# SRK1201L_MODUL_CON.net
KiCad netlist of a schematic drawn in Altium Designer
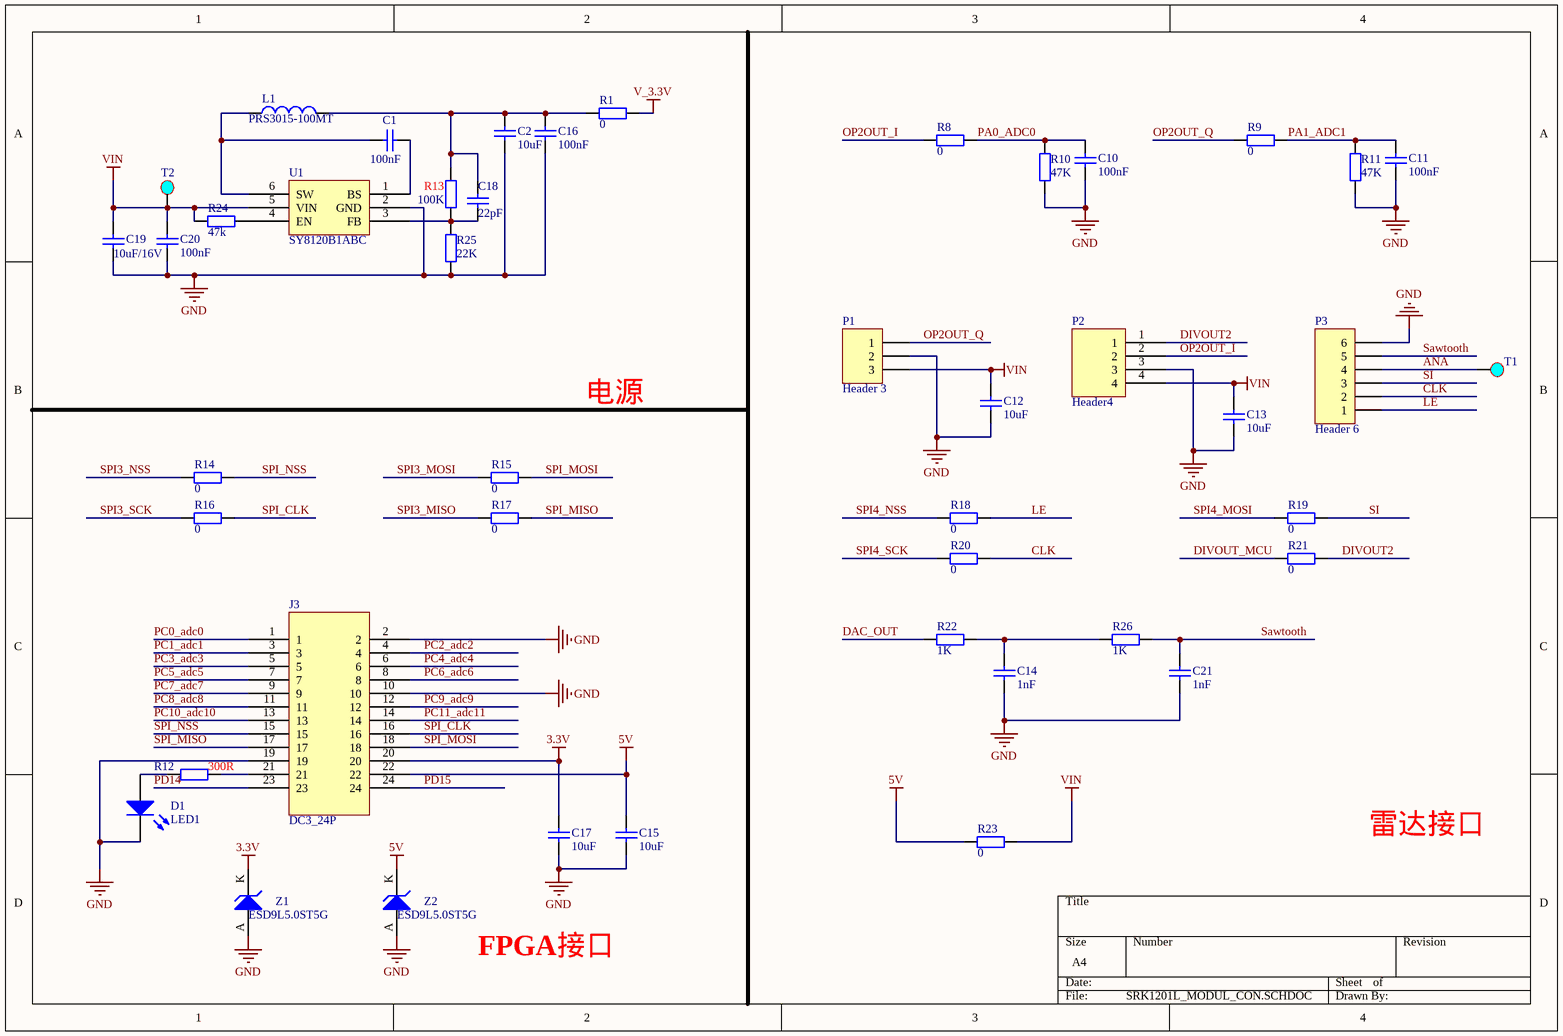
[diagram p0: SRK1201L_MODUL_CON.SCHDOC]

(export (version "E")
  (design (tool "Eeschema 10.0.6"))
  (components
    (comp (ref "C1")
      (value "100nF")
      (footprint "C0402")
      (description "Capacitor")
      (fields (field (name "PUBLISHER") "Altium Limited"))
      (libsource (lib "Miscellaneous Devices") (part "Cap"))
    )
    (comp (ref "C2")
      (value "10uF")
      (footprint "C0603")
      (description "Capacitor")
      (fields (field (name "PUBLISHER") "Altium Limited"))
      (libsource (lib "Miscellaneous Devices") (part "Cap"))
    )
    (comp (ref "C10")
      (value "100nF")
      (footprint "C0402")
      (description "Capacitor")
      (fields (field (name "PUBLISHER") "Altium Limited"))
      (libsource (lib "Miscellaneous Devices") (part "Cap"))
    )
    (comp (ref "C11")
      (value "100nF")
      (footprint "C0402")
      (description "Capacitor")
      (fields (field (name "PUBLISHER") "Altium Limited"))
      (libsource (lib "Miscellaneous Devices") (part "Cap"))
    )
    (comp (ref "C12")
      (value "10uF")
      (footprint "C0603")
      (description "Capacitor")
      (fields (field (name "PUBLISHER") "Altium Limited"))
      (libsource (lib "Miscellaneous Devices") (part "Cap"))
    )
    (comp (ref "C13")
      (value "10uF")
      (footprint "C0603")
      (description "Capacitor")
      (fields (field (name "PUBLISHER") "Altium Limited"))
      (libsource (lib "Miscellaneous Devices") (part "Cap"))
    )
    (comp (ref "C14")
      (value "1nF")
      (footprint "C0402")
      (description "Capacitor")
      (fields (field (name "PUBLISHER") "Altium Limited"))
      (libsource (lib "Miscellaneous Devices") (part "Cap"))
    )
    (comp (ref "C15")
      (value "10uF")
      (footprint "C0603")
      (description "Capacitor")
      (fields (field (name "PUBLISHER") "Altium Limited"))
      (libsource (lib "Miscellaneous Devices") (part "Cap"))
    )
    (comp (ref "C16")
      (value "100nF")
      (footprint "C0402")
      (description "Capacitor")
      (fields (field (name "PUBLISHER") "Altium Limited"))
      (libsource (lib "Miscellaneous Devices") (part "Cap"))
    )
    (comp (ref "C17")
      (value "10uF")
      (footprint "C0603")
      (description "Capacitor")
      (fields (field (name "PUBLISHER") "Altium Limited"))
      (libsource (lib "Miscellaneous Devices") (part "Cap"))
    )
    (comp (ref "C18")
      (value "22pF")
      (footprint "C0402")
      (description "Capacitor")
      (fields (field (name "PUBLISHER") "Altium Limited"))
      (libsource (lib "Miscellaneous Devices") (part "Cap"))
    )
    (comp (ref "C19")
      (value "10uF/16V")
      (footprint "C0603")
      (description "Capacitor")
      (fields (field (name "PUBLISHER") "Altium Limited"))
      (libsource (lib "Miscellaneous Devices") (part "Cap"))
    )
    (comp (ref "C20")
      (value "100nF")
      (footprint "C0402")
      (description "Capacitor")
      (fields (field (name "PUBLISHER") "Altium Limited"))
      (libsource (lib "Miscellaneous Devices") (part "Cap"))
    )
    (comp (ref "C21")
      (value "1nF")
      (footprint "C0402")
      (description "Capacitor")
      (fields (field (name "PUBLISHER") "Altium Limited"))
      (libsource (lib "Miscellaneous Devices") (part "Cap"))
    )
    (comp (ref "D1")
      (value "LED1")
      (footprint "LED-0603")
      (description "Typical RED GaAs LED")
      (fields (field (name "PUBLISHER") "Altium Limited"))
      (libsource (lib "Miscellaneous Devices") (part "LED1"))
    )
    (comp (ref "J3")
      (value "DC3_24P")
      (footprint "CON2.0-12X2 -SWAP")
      (libsource (lib "Schlib1") (part "DC3_24P"))
    )
    (comp (ref "L1")
      (value "PRS3015-100MT")
      (footprint "PRS3015")
      (description "Inductor")
      (fields (field (name "PUBLISHER") "Altium Limited"))
      (libsource (lib "Miscellaneous Devices") (part "Inductor"))
    )
    (comp (ref "P1")
      (value "Header 3")
      (footprint "HDR1X3-2.54")
      (description "Header, 3-Pin")
      (fields (field (name "PUBLISHER") "Altium Limited"))
      (libsource (lib "Miscellaneous Connectors") (part "Header 3"))
    )
    (comp (ref "P2") (value "Header4") (footprint "J4") (libsource (lib "Schlib1") (part "J4")))
    (comp (ref "P3")
      (value "Header 6")
      (footprint "HDR1X6")
      (description "Header, 6-Pin")
      (fields (field (name "PUBLISHER") "Altium Limited"))
      (libsource (lib "Miscellaneous Connectors") (part "Header 6"))
    )
    (comp (ref "R1")
      (value "0")
      (footprint "R0402")
      (description "Resistor")
      (fields (field (name "PUBLISHER") "Altium Limited"))
      (libsource (lib "Miscellaneous Devices") (part "Res2"))
    )
    (comp (ref "R8")
      (value "0")
      (footprint "R0402")
      (description "Resistor")
      (fields (field (name "PUBLISHER") "Altium Limited"))
      (libsource (lib "Miscellaneous Devices") (part "Res2"))
    )
    (comp (ref "R9")
      (value "0")
      (footprint "R0402")
      (description "Resistor")
      (fields (field (name "PUBLISHER") "Altium Limited"))
      (libsource (lib "Miscellaneous Devices") (part "Res2"))
    )
    (comp (ref "R10")
      (value "47K")
      (footprint "R0402")
      (description "Resistor")
      (fields (field (name "PUBLISHER") "Altium Limited"))
      (libsource (lib "") (part "Res2_1"))
    )
    (comp (ref "R11")
      (value "47K")
      (footprint "R0402")
      (description "Resistor")
      (fields (field (name "PUBLISHER") "Altium Limited"))
      (libsource (lib "") (part "Res2_1"))
    )
    (comp (ref "R12")
      (value "300R")
      (footprint "R0402")
      (description "Resistor")
      (fields (field (name "PUBLISHER") "Altium Limited"))
      (libsource (lib "Miscellaneous Devices") (part "Res2"))
    )
    (comp (ref "R13")
      (value "100K")
      (footprint "R0402")
      (description "Resistor")
      (fields (field (name "PUBLISHER") "Altium Limited"))
      (libsource (lib "") (part "Res2_1"))
    )
    (comp (ref "R14")
      (value "0")
      (footprint "R0402")
      (description "Resistor")
      (fields (field (name "PUBLISHER") "Altium Limited"))
      (libsource (lib "Miscellaneous Devices") (part "Res2"))
    )
    (comp (ref "R15")
      (value "0")
      (footprint "R0402")
      (description "Resistor")
      (fields (field (name "PUBLISHER") "Altium Limited"))
      (libsource (lib "Miscellaneous Devices") (part "Res2"))
    )
    (comp (ref "R16")
      (value "0")
      (footprint "R0402")
      (description "Resistor")
      (fields (field (name "PUBLISHER") "Altium Limited"))
      (libsource (lib "Miscellaneous Devices") (part "Res2"))
    )
    (comp (ref "R17")
      (value "0")
      (footprint "R0402")
      (description "Resistor")
      (fields (field (name "PUBLISHER") "Altium Limited"))
      (libsource (lib "Miscellaneous Devices") (part "Res2"))
    )
    (comp (ref "R18")
      (value "0")
      (footprint "R0402")
      (description "Resistor")
      (fields (field (name "PUBLISHER") "Altium Limited"))
      (libsource (lib "Miscellaneous Devices") (part "Res2"))
    )
    (comp (ref "R19")
      (value "0")
      (footprint "R0402")
      (description "Resistor")
      (fields (field (name "PUBLISHER") "Altium Limited"))
      (libsource (lib "Miscellaneous Devices") (part "Res2"))
    )
    (comp (ref "R20")
      (value "0")
      (footprint "R0402")
      (description "Resistor")
      (fields (field (name "PUBLISHER") "Altium Limited"))
      (libsource (lib "Miscellaneous Devices") (part "Res2"))
    )
    (comp (ref "R21")
      (value "0")
      (footprint "R0402")
      (description "Resistor")
      (fields (field (name "PUBLISHER") "Altium Limited"))
      (libsource (lib "Miscellaneous Devices") (part "Res2"))
    )
    (comp (ref "R22")
      (value "1K")
      (footprint "R0402")
      (description "Resistor")
      (fields (field (name "PUBLISHER") "Altium Limited"))
      (libsource (lib "Miscellaneous Devices") (part "Res2"))
    )
    (comp (ref "R23")
      (value "0")
      (footprint "R0402")
      (description "Resistor")
      (fields (field (name "PUBLISHER") "Altium Limited"))
      (libsource (lib "Miscellaneous Devices") (part "Res2"))
    )
    (comp (ref "R24")
      (value "47k")
      (footprint "R0402")
      (description "Resistor")
      (fields (field (name "PUBLISHER") "Altium Limited"))
      (libsource (lib "Miscellaneous Devices") (part "Res2"))
    )
    (comp (ref "R25")
      (value "22K")
      (footprint "R0402")
      (description "Resistor")
      (fields (field (name "PUBLISHER") "Altium Limited"))
      (libsource (lib "") (part "Res2_1"))
    )
    (comp (ref "R26")
      (value "1K")
      (footprint "R0402")
      (description "Resistor")
      (fields (field (name "PUBLISHER") "Altium Limited"))
      (libsource (lib "Miscellaneous Devices") (part "Res2"))
    )
    (comp (ref "T1")
      (value "~")
      (footprint "TestPoints")
      (description "TestPoints")
      (libsource (lib "标准原理图库（特种板）") (part "TestPoints"))
    )
    (comp (ref "T2")
      (value "~")
      (footprint "TestPoints-0.7")
      (description "TestPoints")
      (libsource (lib "标准原理图库（特种板）") (part "TestPoints"))
    )
    (comp (ref "U1") (value "SY8120B1ABC") (footprint "SOT-23-6") (libsource (lib "Schlib1") (part "H9108")))
    (comp (ref "Z1")
      (value "ESD9L5.0ST5G")
      (footprint "SOD-923")
      (description "Zener Diode")
      (fields (field (name "PUBLISHER") "Altium Limited"))
      (libsource (lib "Miscellaneous Devices") (part "D Zener"))
    )
    (comp (ref "Z2")
      (value "ESD9L5.0ST5G")
      (footprint "SOD-923")
      (description "Zener Diode")
      (fields (field (name "PUBLISHER") "Altium Limited"))
      (libsource (lib "Miscellaneous Devices") (part "D Zener"))
    )
  )
  (nets
    (net (code "1") (name "/ANA") (class "Default")
      (node (ref "P3") (pin "4") (pinfunction "4_4") (pintype "passive"))
      (node (ref "T1") (pin "1") (pinfunction "1_1") (pintype "passive"))
    )
    (net (code "2") (name "/CLK") (class "Default")
      (node (ref "P3") (pin "2") (pinfunction "2_2") (pintype "passive"))
      (node (ref "R20") (pin "1") (pinfunction "1_1") (pintype "passive"))
    )
    (net (code "3") (name "/DAC_OUT") (class "Default")
      (node (ref "R22") (pin "2") (pinfunction "2_2") (pintype "passive"))
    )
    (net (code "4") (name "/DIVOUT2") (class "Default")
      (node (ref "P2") (pin "1") (pinfunction "1_1") (pintype "passive"))
      (node (ref "R21") (pin "1") (pinfunction "1_1") (pintype "passive"))
    )
    (net (code "5") (name "/DIVOUT_MCU") (class "Default")
      (node (ref "R21") (pin "2") (pinfunction "2_2") (pintype "passive"))
    )
    (net (code "6") (name "/LE") (class "Default")
      (node (ref "P3") (pin "1") (pinfunction "1_1") (pintype "passive"))
      (node (ref "R18") (pin "1") (pinfunction "1_1") (pintype "passive"))
    )
    (net (code "7") (name "/OP2OUT_I") (class "Default")
      (node (ref "P2") (pin "2") (pinfunction "2_2") (pintype "passive"))
      (node (ref "R8") (pin "2") (pinfunction "2_2") (pintype "passive"))
    )
    (net (code "8") (name "/OP2OUT_Q") (class "Default")
      (node (ref "P1") (pin "1") (pinfunction "1_1") (pintype "passive"))
      (node (ref "R9") (pin "2") (pinfunction "2_2") (pintype "passive"))
    )
    (net (code "9") (name "/PA0_ADC0") (class "Default")
      (node (ref "C10") (pin "1") (pinfunction "1_1") (pintype "passive"))
      (node (ref "R10") (pin "2") (pinfunction "2_2") (pintype "passive"))
      (node (ref "R8") (pin "1") (pinfunction "1_1") (pintype "passive"))
    )
    (net (code "10") (name "/PA1_ADC1") (class "Default")
      (node (ref "C11") (pin "1") (pinfunction "1_1") (pintype "passive"))
      (node (ref "R11") (pin "2") (pinfunction "2_2") (pintype "passive"))
      (node (ref "R9") (pin "1") (pinfunction "1_1") (pintype "passive"))
    )
    (net (code "11") (name "/PC0_adc0") (class "Default")
      (node (ref "J3") (pin "1") (pinfunction "1_1") (pintype "passive"))
    )
    (net (code "12") (name "/PC1_adc1") (class "Default")
      (node (ref "J3") (pin "3") (pinfunction "3_3") (pintype "passive"))
    )
    (net (code "13") (name "/PC2_adc2") (class "Default")
      (node (ref "J3") (pin "4") (pinfunction "4_4") (pintype "passive"))
    )
    (net (code "14") (name "/PC3_adc3") (class "Default")
      (node (ref "J3") (pin "5") (pinfunction "5_5") (pintype "passive"))
    )
    (net (code "15") (name "/PC4_adc4") (class "Default")
      (node (ref "J3") (pin "6") (pinfunction "6_6") (pintype "passive"))
    )
    (net (code "16") (name "/PC5_adc5") (class "Default")
      (node (ref "J3") (pin "7") (pinfunction "7_7") (pintype "passive"))
    )
    (net (code "17") (name "/PC6_adc6") (class "Default")
      (node (ref "J3") (pin "8") (pinfunction "8_8") (pintype "passive"))
    )
    (net (code "18") (name "/PC7_adc7") (class "Default")
      (node (ref "J3") (pin "9") (pinfunction "9_9") (pintype "passive"))
    )
    (net (code "19") (name "/PC8_adc8") (class "Default")
      (node (ref "J3") (pin "11") (pinfunction "11_11") (pintype "passive"))
    )
    (net (code "20") (name "/PC9_adc9") (class "Default")
      (node (ref "J3") (pin "12") (pinfunction "12_12") (pintype "passive"))
    )
    (net (code "21") (name "/PC10_adc10") (class "Default")
      (node (ref "J3") (pin "13") (pinfunction "13_13") (pintype "passive"))
    )
    (net (code "22") (name "/PC11_adc11") (class "Default")
      (node (ref "J3") (pin "14") (pinfunction "14_14") (pintype "passive"))
    )
    (net (code "23") (name "/PD14") (class "Default")
      (node (ref "J3") (pin "23") (pinfunction "23_23") (pintype "passive"))
    )
    (net (code "24") (name "/PD15") (class "Default")
      (node (ref "J3") (pin "24") (pinfunction "24_24") (pintype "passive"))
    )
    (net (code "25") (name "/SI") (class "Default")
      (node (ref "P3") (pin "3") (pinfunction "3_3") (pintype "passive"))
      (node (ref "R19") (pin "1") (pinfunction "1_1") (pintype "passive"))
    )
    (net (code "26") (name "/SPI3_MISO") (class "Default")
      (node (ref "R17") (pin "2") (pinfunction "2_2") (pintype "passive"))
    )
    (net (code "27") (name "/SPI3_MOSI") (class "Default")
      (node (ref "R15") (pin "2") (pinfunction "2_2") (pintype "passive"))
    )
    (net (code "28") (name "/SPI3_NSS") (class "Default")
      (node (ref "R14") (pin "2") (pinfunction "2_2") (pintype "passive"))
    )
    (net (code "29") (name "/SPI3_SCK") (class "Default")
      (node (ref "R16") (pin "2") (pinfunction "2_2") (pintype "passive"))
    )
    (net (code "30") (name "/SPI4_MOSI") (class "Default")
      (node (ref "R19") (pin "2") (pinfunction "2_2") (pintype "passive"))
    )
    (net (code "31") (name "/SPI4_NSS") (class "Default")
      (node (ref "R18") (pin "2") (pinfunction "2_2") (pintype "passive"))
    )
    (net (code "32") (name "/SPI4_SCK") (class "Default")
      (node (ref "R20") (pin "2") (pinfunction "2_2") (pintype "passive"))
    )
    (net (code "33") (name "/SPI_CLK") (class "Default")
      (node (ref "J3") (pin "16") (pinfunction "16_16") (pintype "passive"))
      (node (ref "R16") (pin "1") (pinfunction "1_1") (pintype "passive"))
    )
    (net (code "34") (name "/SPI_MISO") (class "Default")
      (node (ref "J3") (pin "17") (pinfunction "17_17") (pintype "passive"))
      (node (ref "R17") (pin "1") (pinfunction "1_1") (pintype "passive"))
    )
    (net (code "35") (name "/SPI_MOSI") (class "Default")
      (node (ref "J3") (pin "18") (pinfunction "18_18") (pintype "passive"))
      (node (ref "R15") (pin "1") (pinfunction "1_1") (pintype "passive"))
    )
    (net (code "36") (name "/SPI_NSS") (class "Default")
      (node (ref "J3") (pin "15") (pinfunction "15_15") (pintype "passive"))
      (node (ref "R14") (pin "1") (pinfunction "1_1") (pintype "passive"))
    )
    (net (code "37") (name "/Sawtooth") (class "Default")
      (node (ref "C21") (pin "1") (pinfunction "1_1") (pintype "passive"))
      (node (ref "P3") (pin "5") (pinfunction "5_5") (pintype "passive"))
      (node (ref "R26") (pin "1") (pinfunction "1_1") (pintype "passive"))
    )
    (net (code "38") (name "3.3V") (class "Default")
      (node (ref "C17") (pin "1") (pinfunction "1_1") (pintype "passive"))
      (node (ref "J3") (pin "20") (pinfunction "20_20") (pintype "passive"))
      (node (ref "Z1") (pin "K") (pinfunction "K_K") (pintype "passive"))
    )
    (net (code "39") (name "5V") (class "Default")
      (node (ref "C15") (pin "1") (pinfunction "1_1") (pintype "passive"))
      (node (ref "J3") (pin "22") (pinfunction "22_22") (pintype "passive"))
      (node (ref "R23") (pin "2") (pinfunction "2_2") (pintype "passive"))
      (node (ref "Z2") (pin "K") (pinfunction "K_K") (pintype "passive"))
    )
    (net (code "40") (name "GND") (class "Default")
      (node (ref "C10") (pin "2") (pinfunction "2_2") (pintype "passive"))
      (node (ref "C11") (pin "2") (pinfunction "2_2") (pintype "passive"))
      (node (ref "C12") (pin "2") (pinfunction "2_2") (pintype "passive"))
      (node (ref "C13") (pin "2") (pinfunction "2_2") (pintype "passive"))
      (node (ref "C14") (pin "2") (pinfunction "2_2") (pintype "passive"))
      (node (ref "C15") (pin "2") (pinfunction "2_2") (pintype "passive"))
      (node (ref "C16") (pin "1") (pinfunction "1_1") (pintype "passive"))
      (node (ref "C17") (pin "2") (pinfunction "2_2") (pintype "passive"))
      (node (ref "C19") (pin "2") (pinfunction "2_2") (pintype "passive"))
      (node (ref "C2") (pin "2") (pinfunction "2_2") (pintype "passive"))
      (node (ref "C20") (pin "1") (pinfunction "1_1") (pintype "passive"))
      (node (ref "C21") (pin "2") (pinfunction "2_2") (pintype "passive"))
      (node (ref "D1") (pin "2") (pinfunction "K_2") (pintype "passive"))
      (node (ref "J3") (pin "10") (pinfunction "10_10") (pintype "passive"))
      (node (ref "J3") (pin "19") (pinfunction "19_19") (pintype "passive"))
      (node (ref "J3") (pin "2") (pinfunction "2_2") (pintype "passive"))
      (node (ref "P1") (pin "2") (pinfunction "2_2") (pintype "passive"))
      (node (ref "P2") (pin "3") (pinfunction "3_3") (pintype "passive"))
      (node (ref "P3") (pin "6") (pinfunction "6_6") (pintype "passive"))
      (node (ref "R10") (pin "1") (pinfunction "1_1") (pintype "passive"))
      (node (ref "R11") (pin "1") (pinfunction "1_1") (pintype "passive"))
      (node (ref "R25") (pin "1") (pinfunction "1_1") (pintype "passive"))
      (node (ref "U1") (pin "2") (pinfunction "GND_2") (pintype "passive"))
      (node (ref "Z1") (pin "A") (pinfunction "A_A") (pintype "passive"))
      (node (ref "Z2") (pin "A") (pinfunction "A_A") (pintype "passive"))
    )
    (net (code "41") (name "Net-(C14-Pad1)") (class "Default")
      (node (ref "C14") (pin "1") (pinfunction "1_1") (pintype "passive"))
      (node (ref "R22") (pin "1") (pinfunction "1_1") (pintype "passive"))
      (node (ref "R26") (pin "2") (pinfunction "2_2") (pintype "passive"))
    )
    (net (code "42") (name "Net-(C16-Pad2)") (class "Default")
      (node (ref "C16") (pin "2") (pinfunction "2_2") (pintype "passive"))
      (node (ref "C18") (pin "2") (pinfunction "2_2") (pintype "passive"))
      (node (ref "C2") (pin "1") (pinfunction "1_1") (pintype "passive"))
      (node (ref "L1") (pin "2") (pinfunction "2_2") (pintype "passive"))
      (node (ref "R1") (pin "2") (pinfunction "2_2") (pintype "passive"))
      (node (ref "R13") (pin "2") (pinfunction "2_2") (pintype "passive"))
    )
    (net (code "43") (name "Net-(D1-A)") (class "Default")
      (node (ref "D1") (pin "1") (pinfunction "A_1") (pintype "passive"))
      (node (ref "R12") (pin "2") (pinfunction "2_2") (pintype "passive"))
    )
    (net (code "44") (name "Net-(J3-Pad21)") (class "Default")
      (node (ref "J3") (pin "21") (pinfunction "21_21") (pintype "passive"))
      (node (ref "R12") (pin "1") (pinfunction "1_1") (pintype "passive"))
    )
    (net (code "45") (name "Net-(U1-BS)") (class "Default")
      (node (ref "C1") (pin "2") (pinfunction "2_2") (pintype "passive"))
      (node (ref "U1") (pin "1") (pinfunction "BS_1") (pintype "passive"))
    )
    (net (code "46") (name "Net-(U1-EN)") (class "Default")
      (node (ref "R24") (pin "1") (pinfunction "1_1") (pintype "passive"))
      (node (ref "U1") (pin "4") (pinfunction "EN_4") (pintype "passive"))
    )
    (net (code "47") (name "Net-(U1-FB)") (class "Default")
      (node (ref "C18") (pin "1") (pinfunction "1_1") (pintype "passive"))
      (node (ref "R13") (pin "1") (pinfunction "1_1") (pintype "passive"))
      (node (ref "R25") (pin "2") (pinfunction "2_2") (pintype "passive"))
      (node (ref "U1") (pin "3") (pinfunction "FB_3") (pintype "passive"))
    )
    (net (code "48") (name "Net-(U1-SW)") (class "Default")
      (node (ref "C1") (pin "1") (pinfunction "1_1") (pintype "passive"))
      (node (ref "L1") (pin "1") (pinfunction "1_1") (pintype "passive"))
      (node (ref "U1") (pin "6") (pinfunction "SW_6") (pintype "passive"))
    )
    (net (code "49") (name "VIN") (class "Default")
      (node (ref "C12") (pin "1") (pinfunction "1_1") (pintype "passive"))
      (node (ref "C13") (pin "1") (pinfunction "1_1") (pintype "passive"))
      (node (ref "C19") (pin "1") (pinfunction "1_1") (pintype "passive"))
      (node (ref "C20") (pin "2") (pinfunction "2_2") (pintype "passive"))
      (node (ref "P1") (pin "3") (pinfunction "3_3") (pintype "passive"))
      (node (ref "P2") (pin "4") (pinfunction "4_4") (pintype "passive"))
      (node (ref "R23") (pin "1") (pinfunction "1_1") (pintype "passive"))
      (node (ref "R24") (pin "2") (pinfunction "2_2") (pintype "passive"))
      (node (ref "T2") (pin "1") (pinfunction "1_1") (pintype "passive"))
      (node (ref "U1") (pin "5") (pinfunction "VIN_5") (pintype "passive"))
    )
    (net (code "50") (name "V_3.3V") (class "Default")
      (node (ref "R1") (pin "1") (pinfunction "1_1") (pintype "passive"))
    )
  )
)
